# connectors.net
KiCad netlist of a schematic drawn in Altium Designer
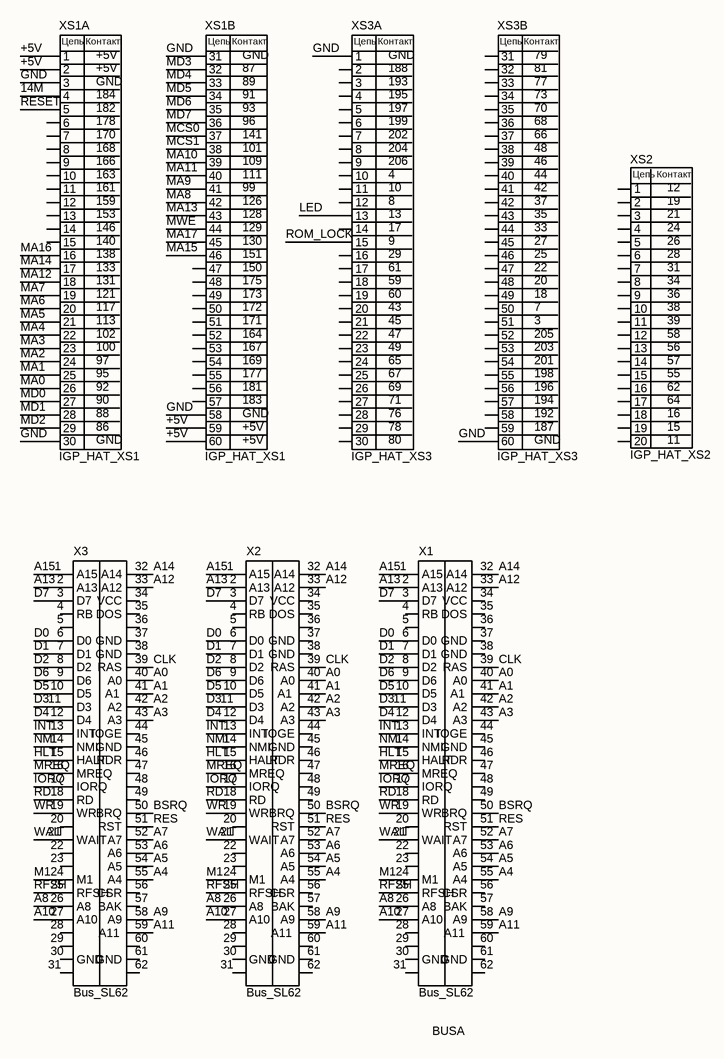
[diagram p0: connectors.SchDoc]

(export (version "E")
  (design (tool "Eeschema 10.0.6"))
  (components
    (comp (ref "X1") (value "Bus_SL62") (footprint "SL62") (libsource (lib "Connectors") (part "Bus_SL62")))
    (comp (ref "X2") (value "Bus_SL62") (footprint "SL62") (libsource (lib "Connectors") (part "Bus_SL62")))
    (comp (ref "X3") (value "Bus_SL62") (footprint "SL62") (libsource (lib "Connectors") (part "Bus_SL62")))
    (comp (ref "XS1")
      (value "IGP_HAT_XS1")
      (footprint "IGP_HAT_XS_60PIN")
      (libsource (lib "cpld") (part "IGP_HAT_XS1"))
    )
    (comp (ref "XS2")
      (value "IGP_HAT_XS2")
      (footprint "IGP_HAT_XS_20PIN")
      (libsource (lib "cpld") (part "IGP_HAT_XS2"))
    )
    (comp (ref "XS3")
      (value "IGP_HAT_XS3")
      (footprint "IGP_HAT_XS_60PIN")
      (libsource (lib "cpld") (part "IGP_HAT_XS3"))
    )
  )
  (nets
    (net (code "1") (name "/+5V") (class "Default")
      (node (ref "XS1") (pin "1") (pinfunction "1_1") (pintype "passive"))
      (node (ref "XS1") (pin "2") (pinfunction "2_2") (pintype "passive"))
      (node (ref "XS1") (pin "59") (pinfunction "59_59") (pintype "passive"))
      (node (ref "XS1") (pin "60") (pinfunction "60_60") (pintype "passive"))
    )
    (net (code "2") (name "/14M") (class "Default")
      (node (ref "XS1") (pin "4") (pinfunction "4_4") (pintype "passive"))
    )
    (net (code "4") (name "/A0") (class "Default")
      (node (ref "X1") (pin "40") (pinfunction "A0_40") (pintype "passive"))
      (node (ref "X2") (pin "40") (pinfunction "A0_40") (pintype "passive"))
      (node (ref "X3") (pin "40") (pinfunction "A0_40") (pintype "passive"))
    )
    (net (code "5") (name "/A1") (class "Default")
      (node (ref "X1") (pin "41") (pinfunction "A1_41") (pintype "passive"))
      (node (ref "X2") (pin "41") (pinfunction "A1_41") (pintype "passive"))
      (node (ref "X3") (pin "41") (pinfunction "A1_41") (pintype "passive"))
    )
    (net (code "6") (name "/A2") (class "Default")
      (node (ref "X1") (pin "42") (pinfunction "A2_42") (pintype "passive"))
      (node (ref "X2") (pin "42") (pinfunction "A2_42") (pintype "passive"))
      (node (ref "X3") (pin "42") (pinfunction "A2_42") (pintype "passive"))
    )
    (net (code "7") (name "/A3") (class "Default")
      (node (ref "X1") (pin "43") (pinfunction "A3_43") (pintype "passive"))
      (node (ref "X2") (pin "43") (pinfunction "A3_43") (pintype "passive"))
      (node (ref "X3") (pin "43") (pinfunction "A3_43") (pintype "passive"))
    )
    (net (code "8") (name "/A4") (class "Default")
      (node (ref "X1") (pin "55") (pinfunction "A4_55") (pintype "passive"))
      (node (ref "X2") (pin "55") (pinfunction "A4_55") (pintype "passive"))
      (node (ref "X3") (pin "55") (pinfunction "A4_55") (pintype "passive"))
    )
    (net (code "9") (name "/A5") (class "Default")
      (node (ref "X1") (pin "54") (pinfunction "A5_54") (pintype "passive"))
      (node (ref "X2") (pin "54") (pinfunction "A5_54") (pintype "passive"))
      (node (ref "X3") (pin "54") (pinfunction "A5_54") (pintype "passive"))
    )
    (net (code "10") (name "/A6") (class "Default")
      (node (ref "X1") (pin "53") (pinfunction "A6_53") (pintype "passive"))
      (node (ref "X2") (pin "53") (pinfunction "A6_53") (pintype "passive"))
      (node (ref "X3") (pin "53") (pinfunction "A6_53") (pintype "passive"))
    )
    (net (code "11") (name "/A7") (class "Default")
      (node (ref "X1") (pin "52") (pinfunction "A7_52") (pintype "passive"))
      (node (ref "X2") (pin "52") (pinfunction "A7_52") (pintype "passive"))
      (node (ref "X3") (pin "52") (pinfunction "A7_52") (pintype "passive"))
    )
    (net (code "12") (name "/A8") (class "Default")
      (node (ref "X1") (pin "26") (pinfunction "A8_26") (pintype "passive"))
      (node (ref "X2") (pin "26") (pinfunction "A8_26") (pintype "passive"))
      (node (ref "X3") (pin "26") (pinfunction "A8_26") (pintype "passive"))
    )
    (net (code "13") (name "/A9") (class "Default")
      (node (ref "X1") (pin "58") (pinfunction "A9_58") (pintype "passive"))
      (node (ref "X2") (pin "58") (pinfunction "A9_58") (pintype "passive"))
      (node (ref "X3") (pin "58") (pinfunction "A9_58") (pintype "passive"))
    )
    (net (code "14") (name "/A10") (class "Default")
      (node (ref "X1") (pin "27") (pinfunction "A10_27") (pintype "passive"))
      (node (ref "X2") (pin "27") (pinfunction "A10_27") (pintype "passive"))
      (node (ref "X3") (pin "27") (pinfunction "A10_27") (pintype "passive"))
    )
    (net (code "15") (name "/A11") (class "Default")
      (node (ref "X1") (pin "59") (pinfunction "A11_59") (pintype "passive"))
      (node (ref "X2") (pin "59") (pinfunction "A11_59") (pintype "passive"))
      (node (ref "X3") (pin "59") (pinfunction "A11_59") (pintype "passive"))
    )
    (net (code "16") (name "/A12") (class "Default")
      (node (ref "X1") (pin "33") (pinfunction "A12_33") (pintype "passive"))
      (node (ref "X2") (pin "33") (pinfunction "A12_33") (pintype "passive"))
      (node (ref "X3") (pin "33") (pinfunction "A12_33") (pintype "passive"))
    )
    (net (code "17") (name "/A13") (class "Default")
      (node (ref "X1") (pin "2") (pinfunction "A13_2") (pintype "passive"))
      (node (ref "X2") (pin "2") (pinfunction "A13_2") (pintype "passive"))
      (node (ref "X3") (pin "2") (pinfunction "A13_2") (pintype "passive"))
    )
    (net (code "18") (name "/A14") (class "Default")
      (node (ref "X1") (pin "32") (pinfunction "A14_32") (pintype "passive"))
      (node (ref "X2") (pin "32") (pinfunction "A14_32") (pintype "passive"))
      (node (ref "X3") (pin "32") (pinfunction "A14_32") (pintype "passive"))
    )
    (net (code "19") (name "/A15") (class "Default")
      (node (ref "X1") (pin "1") (pinfunction "A15_1") (pintype "passive"))
      (node (ref "X2") (pin "1") (pinfunction "A15_1") (pintype "passive"))
      (node (ref "X3") (pin "1") (pinfunction "A15_1") (pintype "passive"))
    )
    (net (code "20") (name "/BSRQ") (class "Default")
      (node (ref "X1") (pin "50") (pinfunction "BRQ_50") (pintype "passive"))
      (node (ref "X2") (pin "50") (pinfunction "BRQ_50") (pintype "passive"))
      (node (ref "X3") (pin "50") (pinfunction "BRQ_50") (pintype "passive"))
    )
    (net (code "22") (name "/CLK") (class "Default")
      (node (ref "X1") (pin "39") (pinfunction "RAS_39") (pintype "passive"))
      (node (ref "X2") (pin "39") (pinfunction "RAS_39") (pintype "passive"))
      (node (ref "X3") (pin "39") (pinfunction "RAS_39") (pintype "passive"))
    )
    (net (code "23") (name "/D0") (class "Default")
      (node (ref "X1") (pin "6") (pinfunction "D0_6") (pintype "passive"))
      (node (ref "X2") (pin "6") (pinfunction "D0_6") (pintype "passive"))
      (node (ref "X3") (pin "6") (pinfunction "D0_6") (pintype "passive"))
    )
    (net (code "24") (name "/D1") (class "Default")
      (node (ref "X1") (pin "7") (pinfunction "D1_7") (pintype "passive"))
      (node (ref "X2") (pin "7") (pinfunction "D1_7") (pintype "passive"))
      (node (ref "X3") (pin "7") (pinfunction "D1_7") (pintype "passive"))
    )
    (net (code "25") (name "/D2") (class "Default")
      (node (ref "X1") (pin "8") (pinfunction "D2_8") (pintype "passive"))
      (node (ref "X2") (pin "8") (pinfunction "D2_8") (pintype "passive"))
      (node (ref "X3") (pin "8") (pinfunction "D2_8") (pintype "passive"))
    )
    (net (code "26") (name "/D3") (class "Default")
      (node (ref "X1") (pin "11") (pinfunction "D3_11") (pintype "passive"))
      (node (ref "X2") (pin "11") (pinfunction "D3_11") (pintype "passive"))
      (node (ref "X3") (pin "11") (pinfunction "D3_11") (pintype "passive"))
    )
    (net (code "27") (name "/D4") (class "Default")
      (node (ref "X1") (pin "12") (pinfunction "D4_12") (pintype "passive"))
      (node (ref "X2") (pin "12") (pinfunction "D4_12") (pintype "passive"))
      (node (ref "X3") (pin "12") (pinfunction "D4_12") (pintype "passive"))
    )
    (net (code "28") (name "/D5") (class "Default")
      (node (ref "X1") (pin "10") (pinfunction "D5_10") (pintype "passive"))
      (node (ref "X2") (pin "10") (pinfunction "D5_10") (pintype "passive"))
      (node (ref "X3") (pin "10") (pinfunction "D5_10") (pintype "passive"))
    )
    (net (code "29") (name "/D6") (class "Default")
      (node (ref "X1") (pin "9") (pinfunction "D6_9") (pintype "passive"))
      (node (ref "X2") (pin "9") (pinfunction "D6_9") (pintype "passive"))
      (node (ref "X3") (pin "9") (pinfunction "D6_9") (pintype "passive"))
    )
    (net (code "30") (name "/D7") (class "Default")
      (node (ref "X1") (pin "3") (pinfunction "D7_3") (pintype "passive"))
      (node (ref "X2") (pin "3") (pinfunction "D7_3") (pintype "passive"))
      (node (ref "X3") (pin "3") (pinfunction "D7_3") (pintype "passive"))
    )
    (net (code "31") (name "/GND") (class "Default")
      (node (ref "XS1") (pin "3") (pinfunction "3_3") (pintype "passive"))
      (node (ref "XS1") (pin "30") (pinfunction "30_30") (pintype "passive"))
      (node (ref "XS1") (pin "31") (pinfunction "31_31") (pintype "passive"))
      (node (ref "XS1") (pin "58") (pinfunction "58_58") (pintype "passive"))
      (node (ref "XS3") (pin "1") (pinfunction "1_1") (pintype "passive"))
      (node (ref "XS3") (pin "60") (pinfunction "60_60") (pintype "passive"))
    )
    (net (code "32") (name "/HLT") (class "Default")
      (node (ref "X1") (pin "15") (pinfunction "HALT_15") (pintype "passive"))
      (node (ref "X2") (pin "15") (pinfunction "HALT_15") (pintype "passive"))
      (node (ref "X3") (pin "15") (pinfunction "HALT_15") (pintype "passive"))
    )
    (net (code "33") (name "/INT") (class "Default")
      (node (ref "X1") (pin "13") (pinfunction "INT_13") (pintype "passive"))
      (node (ref "X2") (pin "13") (pinfunction "INT_13") (pintype "passive"))
      (node (ref "X3") (pin "13") (pinfunction "INT_13") (pintype "passive"))
    )
    (net (code "34") (name "/IORQ") (class "Default")
      (node (ref "X1") (pin "17") (pinfunction "IORQ_17") (pintype "passive"))
      (node (ref "X2") (pin "17") (pinfunction "IORQ_17") (pintype "passive"))
      (node (ref "X3") (pin "17") (pinfunction "IORQ_17") (pintype "passive"))
    )
    (net (code "35") (name "/LED") (class "Default")
      (node (ref "XS3") (pin "13") (pinfunction "13_13") (pintype "passive"))
    )
    (net (code "36") (name "/M1") (class "Default")
      (node (ref "X1") (pin "24") (pinfunction "M1_24") (pintype "passive"))
      (node (ref "X2") (pin "24") (pinfunction "M1_24") (pintype "passive"))
      (node (ref "X3") (pin "24") (pinfunction "M1_24") (pintype "passive"))
    )
    (net (code "37") (name "/MA0") (class "Default")
      (node (ref "XS1") (pin "26") (pinfunction "26_26") (pintype "passive"))
    )
    (net (code "38") (name "/MA1") (class "Default")
      (node (ref "XS1") (pin "25") (pinfunction "25_25") (pintype "passive"))
    )
    (net (code "39") (name "/MA2") (class "Default")
      (node (ref "XS1") (pin "24") (pinfunction "24_24") (pintype "passive"))
    )
    (net (code "40") (name "/MA3") (class "Default")
      (node (ref "XS1") (pin "23") (pinfunction "23_23") (pintype "passive"))
    )
    (net (code "41") (name "/MA4") (class "Default")
      (node (ref "XS1") (pin "22") (pinfunction "22_22") (pintype "passive"))
    )
    (net (code "42") (name "/MA5") (class "Default")
      (node (ref "XS1") (pin "21") (pinfunction "21_21") (pintype "passive"))
    )
    (net (code "43") (name "/MA6") (class "Default")
      (node (ref "XS1") (pin "20") (pinfunction "20_20") (pintype "passive"))
    )
    (net (code "44") (name "/MA7") (class "Default")
      (node (ref "XS1") (pin "19") (pinfunction "19_19") (pintype "passive"))
    )
    (net (code "45") (name "/MA8") (class "Default")
      (node (ref "XS1") (pin "42") (pinfunction "42_42") (pintype "passive"))
    )
    (net (code "46") (name "/MA9") (class "Default")
      (node (ref "XS1") (pin "41") (pinfunction "41_41") (pintype "passive"))
    )
    (net (code "47") (name "/MA10") (class "Default")
      (node (ref "XS1") (pin "39") (pinfunction "39_39") (pintype "passive"))
    )
    (net (code "48") (name "/MA11") (class "Default")
      (node (ref "XS1") (pin "40") (pinfunction "40_40") (pintype "passive"))
    )
    (net (code "49") (name "/MA12") (class "Default")
      (node (ref "XS1") (pin "18") (pinfunction "18_18") (pintype "passive"))
    )
    (net (code "50") (name "/MA13") (class "Default")
      (node (ref "XS1") (pin "43") (pinfunction "43_43") (pintype "passive"))
    )
    (net (code "51") (name "/MA14") (class "Default")
      (node (ref "XS1") (pin "17") (pinfunction "17_17") (pintype "passive"))
    )
    (net (code "52") (name "/MA15") (class "Default")
      (node (ref "XS1") (pin "46") (pinfunction "46_46") (pintype "passive"))
    )
    (net (code "53") (name "/MA16") (class "Default")
      (node (ref "XS1") (pin "16") (pinfunction "16_16") (pintype "passive"))
    )
    (net (code "54") (name "/MA17") (class "Default")
      (node (ref "XS1") (pin "45") (pinfunction "45_45") (pintype "passive"))
    )
    (net (code "55") (name "/MCS0") (class "Default")
      (node (ref "XS1") (pin "37") (pinfunction "37_37") (pintype "passive"))
    )
    (net (code "56") (name "/MCS1") (class "Default")
      (node (ref "XS1") (pin "38") (pinfunction "38_38") (pintype "passive"))
    )
    (net (code "57") (name "/MD0") (class "Default")
      (node (ref "XS1") (pin "27") (pinfunction "27_27") (pintype "passive"))
    )
    (net (code "58") (name "/MD1") (class "Default")
      (node (ref "XS1") (pin "28") (pinfunction "28_28") (pintype "passive"))
    )
    (net (code "59") (name "/MD2") (class "Default")
      (node (ref "XS1") (pin "29") (pinfunction "29_29") (pintype "passive"))
    )
    (net (code "60") (name "/MD3") (class "Default")
      (node (ref "XS1") (pin "32") (pinfunction "32_32") (pintype "passive"))
    )
    (net (code "61") (name "/MD4") (class "Default")
      (node (ref "XS1") (pin "33") (pinfunction "33_33") (pintype "passive"))
    )
    (net (code "62") (name "/MD5") (class "Default")
      (node (ref "XS1") (pin "34") (pinfunction "34_34") (pintype "passive"))
    )
    (net (code "63") (name "/MD6") (class "Default")
      (node (ref "XS1") (pin "35") (pinfunction "35_35") (pintype "passive"))
    )
    (net (code "64") (name "/MD7") (class "Default")
      (node (ref "XS1") (pin "36") (pinfunction "36_36") (pintype "passive"))
    )
    (net (code "65") (name "/MREQ") (class "Default")
      (node (ref "X1") (pin "16") (pinfunction "MREQ_16") (pintype "passive"))
      (node (ref "X2") (pin "16") (pinfunction "MREQ_16") (pintype "passive"))
      (node (ref "X3") (pin "16") (pinfunction "MREQ_16") (pintype "passive"))
    )
    (net (code "66") (name "/MWE") (class "Default")
      (node (ref "XS1") (pin "44") (pinfunction "44_44") (pintype "passive"))
    )
    (net (code "67") (name "/NMI") (class "Default")
      (node (ref "X1") (pin "14") (pinfunction "NMI_14") (pintype "passive"))
      (node (ref "X2") (pin "14") (pinfunction "NMI_14") (pintype "passive"))
      (node (ref "X3") (pin "14") (pinfunction "NMI_14") (pintype "passive"))
    )
    (net (code "68") (name "/RD") (class "Default")
      (node (ref "X1") (pin "18") (pinfunction "RD_18") (pintype "passive"))
      (node (ref "X2") (pin "18") (pinfunction "RD_18") (pintype "passive"))
      (node (ref "X3") (pin "18") (pinfunction "RD_18") (pintype "passive"))
    )
    (net (code "69") (name "/RES") (class "Default")
      (node (ref "X1") (pin "51") (pinfunction "RST_51") (pintype "passive"))
      (node (ref "X2") (pin "51") (pinfunction "RST_51") (pintype "passive"))
      (node (ref "X3") (pin "51") (pinfunction "RST_51") (pintype "passive"))
    )
    (net (code "70") (name "/RESET") (class "Default")
      (node (ref "XS1") (pin "5") (pinfunction "5_5") (pintype "passive"))
    )
    (net (code "71") (name "/RFSH") (class "Default")
      (node (ref "X1") (pin "25") (pinfunction "RFSH_25") (pintype "passive"))
      (node (ref "X2") (pin "25") (pinfunction "RFSH_25") (pintype "passive"))
      (node (ref "X3") (pin "25") (pinfunction "RFSH_25") (pintype "passive"))
    )
    (net (code "72") (name "/ROM_LOCK") (class "Default")
      (node (ref "XS3") (pin "15") (pinfunction "15_15") (pintype "passive"))
    )
    (net (code "73") (name "/WAIT") (class "Default")
      (node (ref "X1") (pin "21") (pinfunction "WAIT_21") (pintype "passive"))
      (node (ref "X2") (pin "21") (pinfunction "WAIT_21") (pintype "passive"))
      (node (ref "X3") (pin "21") (pinfunction "WAIT_21") (pintype "passive"))
    )
    (net (code "74") (name "/WR") (class "Default")
      (node (ref "X1") (pin "19") (pinfunction "WR_19") (pintype "passive"))
      (node (ref "X2") (pin "19") (pinfunction "WR_19") (pintype "passive"))
      (node (ref "X3") (pin "19") (pinfunction "WR_19") (pintype "passive"))
    )
    (net (code "75") (name "unconnected-(X1-BAK-Pad57)") (class "Default")
      (node (ref "X1") (pin "57") (pinfunction "BAK_57") (pintype "passive"))
    )
    (net (code "76") (name "unconnected-(X1-CSR-Pad56)") (class "Default")
      (node (ref "X1") (pin "56") (pinfunction "CSR_56") (pintype "passive"))
    )
    (net (code "77") (name "unconnected-(X1-DOS-Pad35)") (class "Default")
      (node (ref "X1") (pin "35") (pinfunction "DOS_35") (pintype "passive"))
    )
    (net (code "78") (name "unconnected-(X1-GND-Pad30)") (class "Default")
      (node (ref "X1") (pin "30") (pinfunction "GND_30") (pintype "passive"))
    )
    (net (code "79") (name "unconnected-(X1-GND-Pad37)") (class "Default")
      (node (ref "X1") (pin "37") (pinfunction "GND_37") (pintype "passive"))
    )
    (net (code "80") (name "unconnected-(X1-GND-Pad38)") (class "Default")
      (node (ref "X1") (pin "38") (pinfunction "GND_38") (pintype "passive"))
    )
    (net (code "81") (name "unconnected-(X1-GND-Pad45)") (class "Default")
      (node (ref "X1") (pin "45") (pinfunction "GND_45") (pintype "passive"))
    )
    (net (code "82") (name "unconnected-(X1-GND-Pad61)") (class "Default")
      (node (ref "X1") (pin "61") (pinfunction "GND_61") (pintype "passive"))
    )
    (net (code "83") (name "unconnected-(X1-IOGE-Pad44)") (class "Default")
      (node (ref "X1") (pin "44") (pinfunction "IOGE_44") (pintype "passive"))
    )
    (net (code "84") (name "unconnected-(X1-Pad5)") (class "Default")
      (node (ref "X1") (pin "5") (pintype "passive"))
    )
    (net (code "85") (name "unconnected-(X1-Pad20)") (class "Default")
      (node (ref "X1") (pin "20") (pintype "passive"))
    )
    (net (code "86") (name "unconnected-(X1-Pad22)") (class "Default")
      (node (ref "X1") (pin "22") (pintype "passive"))
    )
    (net (code "87") (name "unconnected-(X1-Pad23)") (class "Default")
      (node (ref "X1") (pin "23") (pintype "passive"))
    )
    (net (code "88") (name "unconnected-(X1-Pad28)") (class "Default")
      (node (ref "X1") (pin "28") (pintype "passive"))
    )
    (net (code "89") (name "unconnected-(X1-Pad29)") (class "Default")
      (node (ref "X1") (pin "29") (pintype "passive"))
    )
    (net (code "90") (name "unconnected-(X1-Pad31)") (class "Default")
      (node (ref "X1") (pin "31") (pintype "passive"))
    )
    (net (code "91") (name "unconnected-(X1-Pad36)") (class "Default")
      (node (ref "X1") (pin "36") (pintype "passive"))
    )
    (net (code "92") (name "unconnected-(X1-Pad47)") (class "Default")
      (node (ref "X1") (pin "47") (pintype "passive"))
    )
    (net (code "93") (name "unconnected-(X1-Pad48)") (class "Default")
      (node (ref "X1") (pin "48") (pintype "passive"))
    )
    (net (code "94") (name "unconnected-(X1-Pad49)") (class "Default")
      (node (ref "X1") (pin "49") (pintype "passive"))
    )
    (net (code "95") (name "unconnected-(X1-Pad60)") (class "Default")
      (node (ref "X1") (pin "60") (pintype "passive"))
    )
    (net (code "96") (name "unconnected-(X1-Pad62)") (class "Default")
      (node (ref "X1") (pin "62") (pintype "passive"))
    )
    (net (code "97") (name "unconnected-(X1-RB-Pad4)") (class "Default")
      (node (ref "X1") (pin "4") (pinfunction "RB_4") (pintype "passive"))
    )
    (net (code "98") (name "unconnected-(X1-RDR-Pad46)") (class "Default")
      (node (ref "X1") (pin "46") (pinfunction "RDR_46") (pintype "passive"))
    )
    (net (code "99") (name "unconnected-(X1-VCC-Pad34)") (class "Default")
      (node (ref "X1") (pin "34") (pinfunction "VCC_34") (pintype "passive"))
    )
    (net (code "100") (name "unconnected-(X2-BAK-Pad57)") (class "Default")
      (node (ref "X2") (pin "57") (pinfunction "BAK_57") (pintype "passive"))
    )
    (net (code "101") (name "unconnected-(X2-CSR-Pad56)") (class "Default")
      (node (ref "X2") (pin "56") (pinfunction "CSR_56") (pintype "passive"))
    )
    (net (code "102") (name "unconnected-(X2-DOS-Pad35)") (class "Default")
      (node (ref "X2") (pin "35") (pinfunction "DOS_35") (pintype "passive"))
    )
    (net (code "103") (name "unconnected-(X2-GND-Pad30)") (class "Default")
      (node (ref "X2") (pin "30") (pinfunction "GND_30") (pintype "passive"))
    )
    (net (code "104") (name "unconnected-(X2-GND-Pad37)") (class "Default")
      (node (ref "X2") (pin "37") (pinfunction "GND_37") (pintype "passive"))
    )
    (net (code "105") (name "unconnected-(X2-GND-Pad38)") (class "Default")
      (node (ref "X2") (pin "38") (pinfunction "GND_38") (pintype "passive"))
    )
    (net (code "106") (name "unconnected-(X2-GND-Pad45)") (class "Default")
      (node (ref "X2") (pin "45") (pinfunction "GND_45") (pintype "passive"))
    )
    (net (code "107") (name "unconnected-(X2-GND-Pad61)") (class "Default")
      (node (ref "X2") (pin "61") (pinfunction "GND_61") (pintype "passive"))
    )
    (net (code "108") (name "unconnected-(X2-IOGE-Pad44)") (class "Default")
      (node (ref "X2") (pin "44") (pinfunction "IOGE_44") (pintype "passive"))
    )
    (net (code "109") (name "unconnected-(X2-Pad5)") (class "Default")
      (node (ref "X2") (pin "5") (pintype "passive"))
    )
    (net (code "110") (name "unconnected-(X2-Pad20)") (class "Default")
      (node (ref "X2") (pin "20") (pintype "passive"))
    )
    (net (code "111") (name "unconnected-(X2-Pad22)") (class "Default")
      (node (ref "X2") (pin "22") (pintype "passive"))
    )
    (net (code "112") (name "unconnected-(X2-Pad23)") (class "Default")
      (node (ref "X2") (pin "23") (pintype "passive"))
    )
    (net (code "113") (name "unconnected-(X2-Pad28)") (class "Default")
      (node (ref "X2") (pin "28") (pintype "passive"))
    )
    (net (code "114") (name "unconnected-(X2-Pad29)") (class "Default")
      (node (ref "X2") (pin "29") (pintype "passive"))
    )
    (net (code "115") (name "unconnected-(X2-Pad31)") (class "Default")
      (node (ref "X2") (pin "31") (pintype "passive"))
    )
    (net (code "116") (name "unconnected-(X2-Pad36)") (class "Default")
      (node (ref "X2") (pin "36") (pintype "passive"))
    )
    (net (code "117") (name "unconnected-(X2-Pad47)") (class "Default")
      (node (ref "X2") (pin "47") (pintype "passive"))
    )
    (net (code "118") (name "unconnected-(X2-Pad48)") (class "Default")
      (node (ref "X2") (pin "48") (pintype "passive"))
    )
    (net (code "119") (name "unconnected-(X2-Pad49)") (class "Default")
      (node (ref "X2") (pin "49") (pintype "passive"))
    )
    (net (code "120") (name "unconnected-(X2-Pad60)") (class "Default")
      (node (ref "X2") (pin "60") (pintype "passive"))
    )
    (net (code "121") (name "unconnected-(X2-Pad62)") (class "Default")
      (node (ref "X2") (pin "62") (pintype "passive"))
    )
    (net (code "122") (name "unconnected-(X2-RB-Pad4)") (class "Default")
      (node (ref "X2") (pin "4") (pinfunction "RB_4") (pintype "passive"))
    )
    (net (code "123") (name "unconnected-(X2-RDR-Pad46)") (class "Default")
      (node (ref "X2") (pin "46") (pinfunction "RDR_46") (pintype "passive"))
    )
    (net (code "124") (name "unconnected-(X2-VCC-Pad34)") (class "Default")
      (node (ref "X2") (pin "34") (pinfunction "VCC_34") (pintype "passive"))
    )
    (net (code "125") (name "unconnected-(X3-BAK-Pad57)") (class "Default")
      (node (ref "X3") (pin "57") (pinfunction "BAK_57") (pintype "passive"))
    )
    (net (code "126") (name "unconnected-(X3-CSR-Pad56)") (class "Default")
      (node (ref "X3") (pin "56") (pinfunction "CSR_56") (pintype "passive"))
    )
    (net (code "127") (name "unconnected-(X3-DOS-Pad35)") (class "Default")
      (node (ref "X3") (pin "35") (pinfunction "DOS_35") (pintype "passive"))
    )
    (net (code "128") (name "unconnected-(X3-GND-Pad30)") (class "Default")
      (node (ref "X3") (pin "30") (pinfunction "GND_30") (pintype "passive"))
    )
    (net (code "129") (name "unconnected-(X3-GND-Pad37)") (class "Default")
      (node (ref "X3") (pin "37") (pinfunction "GND_37") (pintype "passive"))
    )
    (net (code "130") (name "unconnected-(X3-GND-Pad38)") (class "Default")
      (node (ref "X3") (pin "38") (pinfunction "GND_38") (pintype "passive"))
    )
    (net (code "131") (name "unconnected-(X3-GND-Pad45)") (class "Default")
      (node (ref "X3") (pin "45") (pinfunction "GND_45") (pintype "passive"))
    )
    (net (code "132") (name "unconnected-(X3-GND-Pad61)") (class "Default")
      (node (ref "X3") (pin "61") (pinfunction "GND_61") (pintype "passive"))
    )
    (net (code "133") (name "unconnected-(X3-IOGE-Pad44)") (class "Default")
      (node (ref "X3") (pin "44") (pinfunction "IOGE_44") (pintype "passive"))
    )
    (net (code "134") (name "unconnected-(X3-Pad5)") (class "Default")
      (node (ref "X3") (pin "5") (pintype "passive"))
    )
    (net (code "135") (name "unconnected-(X3-Pad20)") (class "Default")
      (node (ref "X3") (pin "20") (pintype "passive"))
    )
    (net (code "136") (name "unconnected-(X3-Pad22)") (class "Default")
      (node (ref "X3") (pin "22") (pintype "passive"))
    )
    (net (code "137") (name "unconnected-(X3-Pad23)") (class "Default")
      (node (ref "X3") (pin "23") (pintype "passive"))
    )
    (net (code "138") (name "unconnected-(X3-Pad28)") (class "Default")
      (node (ref "X3") (pin "28") (pintype "passive"))
    )
    (net (code "139") (name "unconnected-(X3-Pad29)") (class "Default")
      (node (ref "X3") (pin "29") (pintype "passive"))
    )
    (net (code "140") (name "unconnected-(X3-Pad31)") (class "Default")
      (node (ref "X3") (pin "31") (pintype "passive"))
    )
    (net (code "141") (name "unconnected-(X3-Pad36)") (class "Default")
      (node (ref "X3") (pin "36") (pintype "passive"))
    )
    (net (code "142") (name "unconnected-(X3-Pad47)") (class "Default")
      (node (ref "X3") (pin "47") (pintype "passive"))
    )
    (net (code "143") (name "unconnected-(X3-Pad48)") (class "Default")
      (node (ref "X3") (pin "48") (pintype "passive"))
    )
    (net (code "144") (name "unconnected-(X3-Pad49)") (class "Default")
      (node (ref "X3") (pin "49") (pintype "passive"))
    )
    (net (code "145") (name "unconnected-(X3-Pad60)") (class "Default")
      (node (ref "X3") (pin "60") (pintype "passive"))
    )
    (net (code "146") (name "unconnected-(X3-Pad62)") (class "Default")
      (node (ref "X3") (pin "62") (pintype "passive"))
    )
    (net (code "147") (name "unconnected-(X3-RB-Pad4)") (class "Default")
      (node (ref "X3") (pin "4") (pinfunction "RB_4") (pintype "passive"))
    )
    (net (code "148") (name "unconnected-(X3-RDR-Pad46)") (class "Default")
      (node (ref "X3") (pin "46") (pinfunction "RDR_46") (pintype "passive"))
    )
    (net (code "149") (name "unconnected-(X3-VCC-Pad34)") (class "Default")
      (node (ref "X3") (pin "34") (pinfunction "VCC_34") (pintype "passive"))
    )
    (net (code "150") (name "unconnected-(XS1-Pad6)") (class "Default")
      (node (ref "XS1") (pin "6") (pinfunction "6_6") (pintype "passive"))
    )
    (net (code "151") (name "unconnected-(XS1-Pad7)") (class "Default")
      (node (ref "XS1") (pin "7") (pinfunction "7_7") (pintype "passive"))
    )
    (net (code "152") (name "unconnected-(XS1-Pad8)") (class "Default")
      (node (ref "XS1") (pin "8") (pinfunction "8_8") (pintype "passive"))
    )
    (net (code "153") (name "unconnected-(XS1-Pad9)") (class "Default")
      (node (ref "XS1") (pin "9") (pinfunction "9_9") (pintype "passive"))
    )
    (net (code "154") (name "unconnected-(XS1-Pad10)") (class "Default")
      (node (ref "XS1") (pin "10") (pinfunction "10_10") (pintype "passive"))
    )
    (net (code "155") (name "unconnected-(XS1-Pad11)") (class "Default")
      (node (ref "XS1") (pin "11") (pinfunction "11_11") (pintype "passive"))
    )
    (net (code "156") (name "unconnected-(XS1-Pad12)") (class "Default")
      (node (ref "XS1") (pin "12") (pinfunction "12_12") (pintype "passive"))
    )
    (net (code "157") (name "unconnected-(XS1-Pad13)") (class "Default")
      (node (ref "XS1") (pin "13") (pinfunction "13_13") (pintype "passive"))
    )
    (net (code "158") (name "unconnected-(XS1-Pad14)") (class "Default")
      (node (ref "XS1") (pin "14") (pinfunction "14_14") (pintype "passive"))
    )
    (net (code "159") (name "unconnected-(XS1-Pad15)") (class "Default")
      (node (ref "XS1") (pin "15") (pinfunction "15_15") (pintype "passive"))
    )
    (net (code "160") (name "unconnected-(XS1-Pad47)") (class "Default")
      (node (ref "XS1") (pin "47") (pinfunction "47_47") (pintype "passive"))
    )
    (net (code "161") (name "unconnected-(XS1-Pad48)") (class "Default")
      (node (ref "XS1") (pin "48") (pinfunction "48_48") (pintype "passive"))
    )
    (net (code "162") (name "unconnected-(XS1-Pad49)") (class "Default")
      (node (ref "XS1") (pin "49") (pinfunction "49_49") (pintype "passive"))
    )
    (net (code "163") (name "unconnected-(XS1-Pad50)") (class "Default")
      (node (ref "XS1") (pin "50") (pinfunction "50_50") (pintype "passive"))
    )
    (net (code "164") (name "unconnected-(XS1-Pad51)") (class "Default")
      (node (ref "XS1") (pin "51") (pinfunction "51_51") (pintype "passive"))
    )
    (net (code "165") (name "unconnected-(XS1-Pad52)") (class "Default")
      (node (ref "XS1") (pin "52") (pinfunction "52_52") (pintype "passive"))
    )
    (net (code "166") (name "unconnected-(XS1-Pad53)") (class "Default")
      (node (ref "XS1") (pin "53") (pinfunction "53_53") (pintype "passive"))
    )
    (net (code "167") (name "unconnected-(XS1-Pad54)") (class "Default")
      (node (ref "XS1") (pin "54") (pinfunction "54_54") (pintype "passive"))
    )
    (net (code "168") (name "unconnected-(XS1-Pad55)") (class "Default")
      (node (ref "XS1") (pin "55") (pinfunction "55_55") (pintype "passive"))
    )
    (net (code "169") (name "unconnected-(XS1-Pad56)") (class "Default")
      (node (ref "XS1") (pin "56") (pinfunction "56_56") (pintype "passive"))
    )
    (net (code "170") (name "unconnected-(XS1-Pad57)") (class "Default")
      (node (ref "XS1") (pin "57") (pinfunction "57_57") (pintype "passive"))
    )
    (net (code "171") (name "unconnected-(XS2-Pad1)") (class "Default")
      (node (ref "XS2") (pin "1") (pinfunction "1_1") (pintype "passive"))
    )
    (net (code "172") (name "unconnected-(XS2-Pad2)") (class "Default")
      (node (ref "XS2") (pin "2") (pinfunction "2_2") (pintype "passive"))
    )
    (net (code "173") (name "unconnected-(XS2-Pad3)") (class "Default")
      (node (ref "XS2") (pin "3") (pinfunction "3_3") (pintype "passive"))
    )
    (net (code "174") (name "unconnected-(XS2-Pad4)") (class "Default")
      (node (ref "XS2") (pin "4") (pinfunction "4_4") (pintype "passive"))
    )
    (net (code "175") (name "unconnected-(XS2-Pad5)") (class "Default")
      (node (ref "XS2") (pin "5") (pinfunction "5_5") (pintype "passive"))
    )
    (net (code "176") (name "unconnected-(XS2-Pad6)") (class "Default")
      (node (ref "XS2") (pin "6") (pinfunction "6_6") (pintype "passive"))
    )
    (net (code "177") (name "unconnected-(XS2-Pad7)") (class "Default")
      (node (ref "XS2") (pin "7") (pinfunction "7_7") (pintype "passive"))
    )
    (net (code "178") (name "unconnected-(XS2-Pad8)") (class "Default")
      (node (ref "XS2") (pin "8") (pinfunction "8_8") (pintype "passive"))
    )
    (net (code "179") (name "unconnected-(XS2-Pad9)") (class "Default")
      (node (ref "XS2") (pin "9") (pinfunction "9_9") (pintype "passive"))
    )
    (net (code "180") (name "unconnected-(XS2-Pad10)") (class "Default")
      (node (ref "XS2") (pin "10") (pinfunction "10_10") (pintype "passive"))
    )
    (net (code "181") (name "unconnected-(XS2-Pad11)") (class "Default")
      (node (ref "XS2") (pin "11") (pinfunction "11_11") (pintype "passive"))
    )
    (net (code "182") (name "unconnected-(XS2-Pad12)") (class "Default")
      (node (ref "XS2") (pin "12") (pinfunction "12_12") (pintype "passive"))
    )
    (net (code "183") (name "unconnected-(XS2-Pad13)") (class "Default")
      (node (ref "XS2") (pin "13") (pinfunction "13_13") (pintype "passive"))
    )
    (net (code "184") (name "unconnected-(XS2-Pad14)") (class "Default")
      (node (ref "XS2") (pin "14") (pinfunction "14_14") (pintype "passive"))
    )
    (net (code "185") (name "unconnected-(XS2-Pad15)") (class "Default")
      (node (ref "XS2") (pin "15") (pinfunction "15_15") (pintype "passive"))
    )
    (net (code "186") (name "unconnected-(XS2-Pad16)") (class "Default")
      (node (ref "XS2") (pin "16") (pinfunction "16_16") (pintype "passive"))
    )
    (net (code "187") (name "unconnected-(XS2-Pad17)") (class "Default")
      (node (ref "XS2") (pin "17") (pinfunction "17_17") (pintype "passive"))
    )
    (net (code "188") (name "unconnected-(XS2-Pad18)") (class "Default")
      (node (ref "XS2") (pin "18") (pinfunction "18_18") (pintype "passive"))
    )
    (net (code "189") (name "unconnected-(XS2-Pad19)") (class "Default")
      (node (ref "XS2") (pin "19") (pinfunction "19_19") (pintype "passive"))
    )
    (net (code "190") (name "unconnected-(XS2-Pad20)") (class "Default")
      (node (ref "XS2") (pin "20") (pinfunction "20_20") (pintype "passive"))
    )
    (net (code "191") (name "unconnected-(XS3-Pad2)") (class "Default")
      (node (ref "XS3") (pin "2") (pinfunction "2_2") (pintype "passive"))
    )
    (net (code "192") (name "unconnected-(XS3-Pad3)") (class "Default")
      (node (ref "XS3") (pin "3") (pinfunction "3_3") (pintype "passive"))
    )
    (net (code "193") (name "unconnected-(XS3-Pad4)") (class "Default")
      (node (ref "XS3") (pin "4") (pinfunction "4_4") (pintype "passive"))
    )
    (net (code "194") (name "unconnected-(XS3-Pad5)") (class "Default")
      (node (ref "XS3") (pin "5") (pinfunction "5_5") (pintype "passive"))
    )
    (net (code "195") (name "unconnected-(XS3-Pad6)") (class "Default")
      (node (ref "XS3") (pin "6") (pinfunction "6_6") (pintype "passive"))
    )
    (net (code "196") (name "unconnected-(XS3-Pad7)") (class "Default")
      (node (ref "XS3") (pin "7") (pinfunction "7_7") (pintype "passive"))
    )
    (net (code "197") (name "unconnected-(XS3-Pad8)") (class "Default")
      (node (ref "XS3") (pin "8") (pinfunction "8_8") (pintype "passive"))
    )
    (net (code "198") (name "unconnected-(XS3-Pad9)") (class "Default")
      (node (ref "XS3") (pin "9") (pinfunction "9_9") (pintype "passive"))
    )
    (net (code "199") (name "unconnected-(XS3-Pad10)") (class "Default")
      (node (ref "XS3") (pin "10") (pinfunction "10_10") (pintype "passive"))
    )
    (net (code "200") (name "unconnected-(XS3-Pad11)") (class "Default")
      (node (ref "XS3") (pin "11") (pinfunction "11_11") (pintype "passive"))
    )
    (net (code "201") (name "unconnected-(XS3-Pad12)") (class "Default")
      (node (ref "XS3") (pin "12") (pinfunction "12_12") (pintype "passive"))
    )
    (net (code "202") (name "unconnected-(XS3-Pad14)") (class "Default")
      (node (ref "XS3") (pin "14") (pinfunction "14_14") (pintype "passive"))
    )
    (net (code "203") (name "unconnected-(XS3-Pad16)") (class "Default")
      (node (ref "XS3") (pin "16") (pinfunction "16_16") (pintype "passive"))
    )
    (net (code "204") (name "unconnected-(XS3-Pad17)") (class "Default")
      (node (ref "XS3") (pin "17") (pinfunction "17_17") (pintype "passive"))
    )
    (net (code "205") (name "unconnected-(XS3-Pad18)") (class "Default")
      (node (ref "XS3") (pin "18") (pinfunction "18_18") (pintype "passive"))
    )
    (net (code "206") (name "unconnected-(XS3-Pad19)") (class "Default")
      (node (ref "XS3") (pin "19") (pinfunction "19_19") (pintype "passive"))
    )
    (net (code "207") (name "unconnected-(XS3-Pad20)") (class "Default")
      (node (ref "XS3") (pin "20") (pinfunction "20_20") (pintype "passive"))
    )
    (net (code "208") (name "unconnected-(XS3-Pad21)") (class "Default")
      (node (ref "XS3") (pin "21") (pinfunction "21_21") (pintype "passive"))
    )
    (net (code "209") (name "unconnected-(XS3-Pad22)") (class "Default")
      (node (ref "XS3") (pin "22") (pinfunction "22_22") (pintype "passive"))
    )
    (net (code "210") (name "unconnected-(XS3-Pad23)") (class "Default")
      (node (ref "XS3") (pin "23") (pinfunction "23_23") (pintype "passive"))
    )
    (net (code "211") (name "unconnected-(XS3-Pad24)") (class "Default")
      (node (ref "XS3") (pin "24") (pinfunction "24_24") (pintype "passive"))
    )
    (net (code "212") (name "unconnected-(XS3-Pad25)") (class "Default")
      (node (ref "XS3") (pin "25") (pinfunction "25_25") (pintype "passive"))
    )
    (net (code "213") (name "unconnected-(XS3-Pad26)") (class "Default")
      (node (ref "XS3") (pin "26") (pinfunction "26_26") (pintype "passive"))
    )
    (net (code "214") (name "unconnected-(XS3-Pad27)") (class "Default")
      (node (ref "XS3") (pin "27") (pinfunction "27_27") (pintype "passive"))
    )
    (net (code "215") (name "unconnected-(XS3-Pad28)") (class "Default")
      (node (ref "XS3") (pin "28") (pinfunction "28_28") (pintype "passive"))
    )
    (net (code "216") (name "unconnected-(XS3-Pad29)") (class "Default")
      (node (ref "XS3") (pin "29") (pinfunction "29_29") (pintype "passive"))
    )
    (net (code "217") (name "unconnected-(XS3-Pad30)") (class "Default")
      (node (ref "XS3") (pin "30") (pinfunction "30_30") (pintype "passive"))
    )
    (net (code "218") (name "unconnected-(XS3-Pad31)") (class "Default")
      (node (ref "XS3") (pin "31") (pinfunction "31_31") (pintype "passive"))
    )
    (net (code "219") (name "unconnected-(XS3-Pad32)") (class "Default")
      (node (ref "XS3") (pin "32") (pinfunction "32_32") (pintype "passive"))
    )
    (net (code "220") (name "unconnected-(XS3-Pad33)") (class "Default")
      (node (ref "XS3") (pin "33") (pinfunction "33_33") (pintype "passive"))
    )
    (net (code "221") (name "unconnected-(XS3-Pad34)") (class "Default")
      (node (ref "XS3") (pin "34") (pinfunction "34_34") (pintype "passive"))
    )
    (net (code "222") (name "unconnected-(XS3-Pad35)") (class "Default")
      (node (ref "XS3") (pin "35") (pinfunction "35_35") (pintype "passive"))
    )
    (net (code "223") (name "unconnected-(XS3-Pad36)") (class "Default")
      (node (ref "XS3") (pin "36") (pinfunction "36_36") (pintype "passive"))
    )
    (net (code "224") (name "unconnected-(XS3-Pad37)") (class "Default")
      (node (ref "XS3") (pin "37") (pinfunction "37_37") (pintype "passive"))
    )
    (net (code "225") (name "unconnected-(XS3-Pad38)") (class "Default")
      (node (ref "XS3") (pin "38") (pinfunction "38_38") (pintype "passive"))
    )
    (net (code "226") (name "unconnected-(XS3-Pad39)") (class "Default")
      (node (ref "XS3") (pin "39") (pinfunction "39_39") (pintype "passive"))
    )
    (net (code "227") (name "unconnected-(XS3-Pad40)") (class "Default")
      (node (ref "XS3") (pin "40") (pinfunction "40_40") (pintype "passive"))
    )
    (net (code "228") (name "unconnected-(XS3-Pad41)") (class "Default")
      (node (ref "XS3") (pin "41") (pinfunction "41_41") (pintype "passive"))
    )
    (net (code "229") (name "unconnected-(XS3-Pad42)") (class "Default")
      (node (ref "XS3") (pin "42") (pinfunction "42_42") (pintype "passive"))
    )
    (net (code "230") (name "unconnected-(XS3-Pad43)") (class "Default")
      (node (ref "XS3") (pin "43") (pinfunction "43_43") (pintype "passive"))
    )
    (net (code "231") (name "unconnected-(XS3-Pad44)") (class "Default")
      (node (ref "XS3") (pin "44") (pinfunction "44_44") (pintype "passive"))
    )
    (net (code "232") (name "unconnected-(XS3-Pad45)") (class "Default")
      (node (ref "XS3") (pin "45") (pinfunction "45_45") (pintype "passive"))
    )
    (net (code "233") (name "unconnected-(XS3-Pad46)") (class "Default")
      (node (ref "XS3") (pin "46") (pinfunction "46_46") (pintype "passive"))
    )
    (net (code "234") (name "unconnected-(XS3-Pad47)") (class "Default")
      (node (ref "XS3") (pin "47") (pinfunction "47_47") (pintype "passive"))
    )
    (net (code "235") (name "unconnected-(XS3-Pad48)") (class "Default")
      (node (ref "XS3") (pin "48") (pinfunction "48_48") (pintype "passive"))
    )
    (net (code "236") (name "unconnected-(XS3-Pad49)") (class "Default")
      (node (ref "XS3") (pin "49") (pinfunction "49_49") (pintype "passive"))
    )
    (net (code "237") (name "unconnected-(XS3-Pad50)") (class "Default")
      (node (ref "XS3") (pin "50") (pinfunction "50_50") (pintype "passive"))
    )
    (net (code "238") (name "unconnected-(XS3-Pad51)") (class "Default")
      (node (ref "XS3") (pin "51") (pinfunction "51_51") (pintype "passive"))
    )
    (net (code "239") (name "unconnected-(XS3-Pad52)") (class "Default")
      (node (ref "XS3") (pin "52") (pinfunction "52_52") (pintype "passive"))
    )
    (net (code "240") (name "unconnected-(XS3-Pad53)") (class "Default")
      (node (ref "XS3") (pin "53") (pinfunction "53_53") (pintype "passive"))
    )
    (net (code "241") (name "unconnected-(XS3-Pad54)") (class "Default")
      (node (ref "XS3") (pin "54") (pinfunction "54_54") (pintype "passive"))
    )
    (net (code "242") (name "unconnected-(XS3-Pad55)") (class "Default")
      (node (ref "XS3") (pin "55") (pinfunction "55_55") (pintype "passive"))
    )
    (net (code "243") (name "unconnected-(XS3-Pad56)") (class "Default")
      (node (ref "XS3") (pin "56") (pinfunction "56_56") (pintype "passive"))
    )
    (net (code "244") (name "unconnected-(XS3-Pad57)") (class "Default")
      (node (ref "XS3") (pin "57") (pinfunction "57_57") (pintype "passive"))
    )
    (net (code "245") (name "unconnected-(XS3-Pad58)") (class "Default")
      (node (ref "XS3") (pin "58") (pinfunction "58_58") (pintype "passive"))
    )
    (net (code "246") (name "unconnected-(XS3-Pad59)") (class "Default")
      (node (ref "XS3") (pin "59") (pinfunction "59_59") (pintype "passive"))
    )
  )
)
